# Touch_Shield-v20.net
KiCad netlist of a schematic drawn in EAGLE
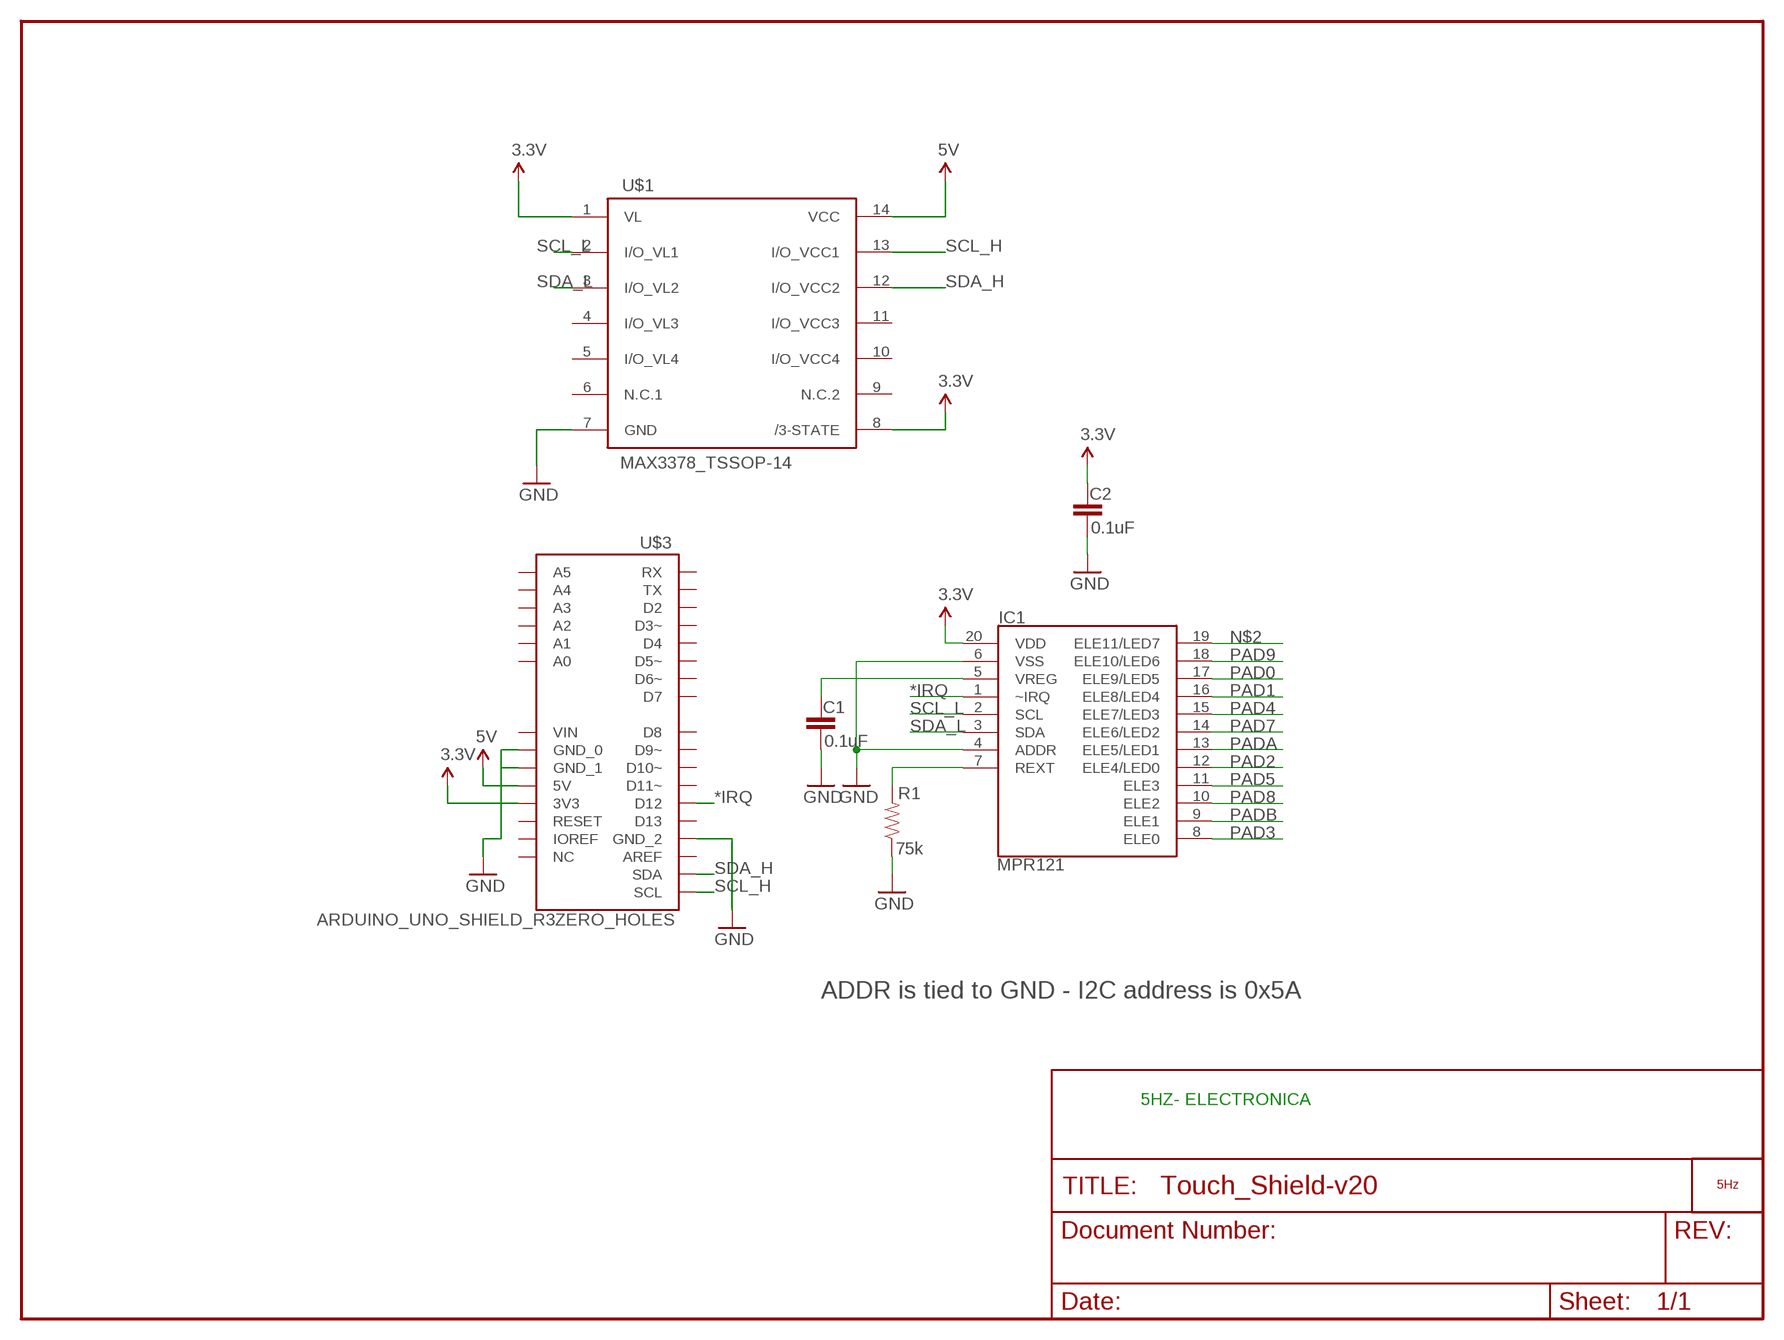
[diagram p0: schematic, sheet 1]

(export (version "E")
  (design (tool "Eeschema 10.0.6"))
  (components
    (comp (ref "C1")
      (value "0.1uF")
      (footprint "eagle-import:0402-CAP")
      (libsource (lib "eagle-import") (part "CAP0402-CAP"))
    )
    (comp (ref "C2")
      (value "0.1uF")
      (footprint "eagle-import:0402-CAP")
      (libsource (lib "eagle-import") (part "CAP0402-CAP"))
    )
    (comp (ref "IC1")
      (value "MPR121")
      (footprint "eagle-import:QFN-20-0.4MM")
      (libsource (lib "eagle-import") (part "MPR121QFN20"))
    )
    (comp (ref "LOGO1")
      (value "LOGO_5HZ_H_10MM")
      (footprint "eagle-import:5HZ_LOGO_H_10MM")
      (libsource (lib "eagle-import") (part "LOGO_5HZ_H_10MM"))
    )
    (comp (ref "R1")
      (value "75k")
      (footprint "eagle-import:0402-RES")
      (libsource (lib "eagle-import") (part "RESISTOR0402-RES"))
    )
    (comp (ref "U$1")
      (value "MAX3378_TSSOP-14")
      (footprint "eagle-import:TSSOP14")
      (libsource (lib "eagle-import") (part "MAX3378_TSSOP-14"))
    )
    (comp (ref "U$3")
      (value "ARDUINO_UNO_SHIELD_R3ZERO_HOLES")
      (footprint "eagle-import:UNO_R3_SHIELD_NO_SILK")
      (libsource (lib "eagle-import") (part "ARDUINO_UNO_SHIELD_R3ZERO_HOLES"))
    )
  )
  (nets
    (net (code "1") (name "/*IRQ") (class "Default")
      (node (ref "IC1") (pin "1") (pinfunction "~{IRQ}_1") (pintype "bidirectional"))
      (node (ref "U$3") (pin "D12") (pinfunction "D12_D12") (pintype "bidirectional"))
    )
    (net (code "2") (name "/N$2") (class "Default")
      (node (ref "IC1") (pin "19") (pinfunction "ELE11/LED7_19") (pintype "bidirectional"))
    )
    (net (code "3") (name "/PAD0") (class "Default")
      (node (ref "IC1") (pin "17") (pinfunction "ELE9/LED5_17") (pintype "bidirectional"))
    )
    (net (code "4") (name "/PAD1") (class "Default")
      (node (ref "IC1") (pin "16") (pinfunction "ELE8/LED4_16") (pintype "bidirectional"))
    )
    (net (code "5") (name "/PAD2") (class "Default")
      (node (ref "IC1") (pin "12") (pinfunction "ELE4/LED0_12") (pintype "bidirectional"))
    )
    (net (code "6") (name "/PAD3") (class "Default")
      (node (ref "IC1") (pin "8") (pinfunction "ELE0_8") (pintype "bidirectional"))
    )
    (net (code "7") (name "/PAD4") (class "Default")
      (node (ref "IC1") (pin "15") (pinfunction "ELE7/LED3_15") (pintype "bidirectional"))
    )
    (net (code "8") (name "/PAD5") (class "Default")
      (node (ref "IC1") (pin "11") (pinfunction "ELE3_11") (pintype "bidirectional"))
    )
    (net (code "9") (name "/PAD7") (class "Default")
      (node (ref "IC1") (pin "14") (pinfunction "ELE6/LED2_14") (pintype "bidirectional"))
    )
    (net (code "10") (name "/PAD8") (class "Default")
      (node (ref "IC1") (pin "10") (pinfunction "ELE2_10") (pintype "bidirectional"))
    )
    (net (code "11") (name "/PAD9") (class "Default")
      (node (ref "IC1") (pin "18") (pinfunction "ELE10/LED6_18") (pintype "bidirectional"))
    )
    (net (code "12") (name "/PADA") (class "Default")
      (node (ref "IC1") (pin "13") (pinfunction "ELE5/LED1_13") (pintype "bidirectional"))
    )
    (net (code "13") (name "/PADB") (class "Default")
      (node (ref "IC1") (pin "9") (pinfunction "ELE1_9") (pintype "bidirectional"))
    )
    (net (code "14") (name "/SCL_H") (class "Default")
      (node (ref "U$1") (pin "13") (pinfunction "I/O_VCC1_13") (pintype "bidirectional"))
      (node (ref "U$3") (pin "SCL") (pinfunction "SCL_SCL") (pintype "bidirectional"))
    )
    (net (code "15") (name "/SCL_L") (class "Default")
      (node (ref "IC1") (pin "2") (pinfunction "SCL_2") (pintype "bidirectional"))
      (node (ref "U$1") (pin "2") (pinfunction "I/O_VL1_2") (pintype "bidirectional"))
    )
    (net (code "16") (name "/SDA_H") (class "Default")
      (node (ref "U$1") (pin "12") (pinfunction "I/O_VCC2_12") (pintype "bidirectional"))
      (node (ref "U$3") (pin "SDA") (pinfunction "SDA_SDA") (pintype "bidirectional"))
    )
    (net (code "17") (name "/SDA_L") (class "Default")
      (node (ref "IC1") (pin "3") (pinfunction "SDA_3") (pintype "bidirectional"))
      (node (ref "U$1") (pin "3") (pinfunction "I/O_VL2_3") (pintype "bidirectional"))
    )
    (net (code "18") (name "3.3V") (class "Default")
      (node (ref "C2") (pin "1") (pinfunction "1_1") (pintype "passive"))
      (node (ref "IC1") (pin "20") (pinfunction "VDD_20") (pintype "bidirectional"))
      (node (ref "U$1") (pin "1") (pinfunction "VL_1") (pintype "power_in"))
      (node (ref "U$1") (pin "8") (pinfunction "/3-STATE_8") (pintype "input"))
      (node (ref "U$3") (pin "3.3V") (pinfunction "3V3_3.3V") (pintype "bidirectional"))
    )
    (net (code "19") (name "5V") (class "Default")
      (node (ref "U$1") (pin "14") (pinfunction "VCC_14") (pintype "power_in"))
      (node (ref "U$3") (pin "5V") (pinfunction "5V_5V") (pintype "bidirectional"))
    )
    (net (code "20") (name "GND") (class "Default")
      (node (ref "C1") (pin "2") (pinfunction "2_2") (pintype "passive"))
      (node (ref "C2") (pin "2") (pinfunction "2_2") (pintype "passive"))
      (node (ref "IC1") (pin "4") (pinfunction "ADDR_4") (pintype "bidirectional"))
      (node (ref "IC1") (pin "6") (pinfunction "VSS_6") (pintype "bidirectional"))
      (node (ref "R1") (pin "1") (pinfunction "1_1") (pintype "passive"))
      (node (ref "U$1") (pin "7") (pinfunction "GND_7") (pintype "power_in"))
      (node (ref "U$3") (pin "GND_0") (pinfunction "GND_0_GND_0") (pintype "bidirectional"))
      (node (ref "U$3") (pin "GND_1") (pinfunction "GND_1_GND_1") (pintype "bidirectional"))
      (node (ref "U$3") (pin "GND_2") (pinfunction "GND_2_GND_2") (pintype "bidirectional"))
    )
    (net (code "21") (name "Net-(IC1-REXT)") (class "Default")
      (node (ref "IC1") (pin "7") (pinfunction "REXT_7") (pintype "bidirectional"))
      (node (ref "R1") (pin "2") (pinfunction "2_2") (pintype "passive"))
    )
    (net (code "22") (name "Net-(IC1-VREG)") (class "Default")
      (node (ref "C1") (pin "1") (pinfunction "1_1") (pintype "passive"))
      (node (ref "IC1") (pin "5") (pinfunction "VREG_5") (pintype "bidirectional"))
    )
    (net (code "23") (name "unconnected-(U$1-I{slash}O_VCC3-Pad11)") (class "Default")
      (node (ref "U$1") (pin "11") (pinfunction "I/O_VCC3_11") (pintype "bidirectional"))
    )
    (net (code "24") (name "unconnected-(U$1-I{slash}O_VCC4-Pad10)") (class "Default")
      (node (ref "U$1") (pin "10") (pinfunction "I/O_VCC4_10") (pintype "bidirectional"))
    )
    (net (code "25") (name "unconnected-(U$1-I{slash}O_VL3-Pad4)") (class "Default")
      (node (ref "U$1") (pin "4") (pinfunction "I/O_VL3_4") (pintype "bidirectional"))
    )
    (net (code "26") (name "unconnected-(U$1-I{slash}O_VL4-Pad5)") (class "Default")
      (node (ref "U$1") (pin "5") (pinfunction "I/O_VL4_5") (pintype "bidirectional"))
    )
    (net (code "27") (name "unconnected-(U$1-N.C.1-Pad6)") (class "Default")
      (node (ref "U$1") (pin "6") (pinfunction "N.C.1_6") (pintype "no_connect"))
    )
    (net (code "28") (name "unconnected-(U$1-N.C.2-Pad9)") (class "Default")
      (node (ref "U$1") (pin "9") (pinfunction "N.C.2_9") (pintype "no_connect"))
    )
    (net (code "29") (name "unconnected-(U$3-D3~{}-PadD3)") (class "Default")
      (node (ref "U$3") (pin "D3") (pinfunction "D3~{}_D3") (pintype "bidirectional"))
    )
    (net (code "30") (name "unconnected-(U$3-D5~{}-PadD5)") (class "Default")
      (node (ref "U$3") (pin "D5") (pinfunction "D5~{}_D5") (pintype "bidirectional"))
    )
    (net (code "31") (name "unconnected-(U$3-D6~{}-PadD6)") (class "Default")
      (node (ref "U$3") (pin "D6") (pinfunction "D6~{}_D6") (pintype "bidirectional"))
    )
    (net (code "32") (name "unconnected-(U$3-D9~{}-PadD9)") (class "Default")
      (node (ref "U$3") (pin "D9") (pinfunction "D9~{}_D9") (pintype "bidirectional"))
    )
    (net (code "33") (name "unconnected-(U$3-D10~{}-PadD10)") (class "Default")
      (node (ref "U$3") (pin "D10") (pinfunction "D10~{}_D10") (pintype "bidirectional"))
    )
    (net (code "34") (name "unconnected-(U$3-D11~{}-PadD11)") (class "Default")
      (node (ref "U$3") (pin "D11") (pinfunction "D11~{}_D11") (pintype "bidirectional"))
    )
    (net (code "35") (name "unconnected-(U$3-PadA0)") (class "Default")
      (node (ref "U$3") (pin "A0") (pinfunction "A0_A0") (pintype "bidirectional"))
    )
    (net (code "36") (name "unconnected-(U$3-PadA1)") (class "Default")
      (node (ref "U$3") (pin "A1") (pinfunction "A1_A1") (pintype "bidirectional"))
    )
    (net (code "37") (name "unconnected-(U$3-PadA2)") (class "Default")
      (node (ref "U$3") (pin "A2") (pinfunction "A2_A2") (pintype "bidirectional"))
    )
    (net (code "38") (name "unconnected-(U$3-PadA3)") (class "Default")
      (node (ref "U$3") (pin "A3") (pinfunction "A3_A3") (pintype "bidirectional"))
    )
    (net (code "39") (name "unconnected-(U$3-PadA4)") (class "Default")
      (node (ref "U$3") (pin "A4") (pinfunction "A4_A4") (pintype "bidirectional"))
    )
    (net (code "40") (name "unconnected-(U$3-PadA5)") (class "Default")
      (node (ref "U$3") (pin "A5") (pinfunction "A5_A5") (pintype "bidirectional"))
    )
    (net (code "41") (name "unconnected-(U$3-PadAREF)") (class "Default")
      (node (ref "U$3") (pin "AREF") (pinfunction "AREF_AREF") (pintype "bidirectional"))
    )
    (net (code "42") (name "unconnected-(U$3-PadD2)") (class "Default")
      (node (ref "U$3") (pin "D2") (pinfunction "D2_D2") (pintype "bidirectional"))
    )
    (net (code "43") (name "unconnected-(U$3-PadD4)") (class "Default")
      (node (ref "U$3") (pin "D4") (pinfunction "D4_D4") (pintype "bidirectional"))
    )
    (net (code "44") (name "unconnected-(U$3-PadD7)") (class "Default")
      (node (ref "U$3") (pin "D7") (pinfunction "D7_D7") (pintype "bidirectional"))
    )
    (net (code "45") (name "unconnected-(U$3-PadD8)") (class "Default")
      (node (ref "U$3") (pin "D8") (pinfunction "D8_D8") (pintype "bidirectional"))
    )
    (net (code "46") (name "unconnected-(U$3-PadD13)") (class "Default")
      (node (ref "U$3") (pin "D13") (pinfunction "D13_D13") (pintype "bidirectional"))
    )
    (net (code "47") (name "unconnected-(U$3-PadIOREF)") (class "Default")
      (node (ref "U$3") (pin "IOREF") (pinfunction "IOREF_IOREF") (pintype "bidirectional"))
    )
    (net (code "48") (name "unconnected-(U$3-PadNC)") (class "Default")
      (node (ref "U$3") (pin "NC") (pinfunction "NC_NC") (pintype "no_connect"))
    )
    (net (code "49") (name "unconnected-(U$3-PadRX)") (class "Default")
      (node (ref "U$3") (pin "RX") (pinfunction "RX_RX") (pintype "bidirectional"))
    )
    (net (code "50") (name "unconnected-(U$3-PadTX)") (class "Default")
      (node (ref "U$3") (pin "TX") (pinfunction "TX_TX") (pintype "bidirectional"))
    )
    (net (code "51") (name "unconnected-(U$3-PadVIN)") (class "Default")
      (node (ref "U$3") (pin "VIN") (pinfunction "VIN_VIN") (pintype "bidirectional"))
    )
    (net (code "52") (name "unconnected-(U$3-RESET-PadRES)") (class "Default")
      (node (ref "U$3") (pin "RES") (pinfunction "RESET_RES") (pintype "bidirectional"))
    )
  )
)
